# SunS_top.net
KiCad netlist of a schematic drawn in Altium Designer
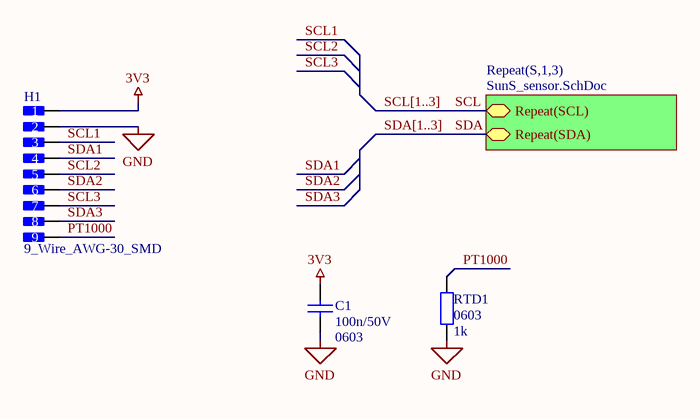
[diagram p0: SunS_top.SchDoc]

(export (version "E")
  (design (tool "Eeschema 10.0.6"))
  (components
    (comp (ref "C1")
      (value "100n/50V")
      (footprint "SMD_Capacitor_0603")
      (description "Ceramic Cap Kemet COTS 100n/50V X7R 0603")
      (fields
        (field (name "MANUFACTURER") "Kemet")
        (field (name "MANUFACTURERPARTNUMBER") "C0603T104K5RALTU")
        (field (name "PACKAGE") "0603")
      )
      (libsource (lib "capacitors") (part "Cer_C0603T104K5RALTU"))
    )
    (comp (ref "H1")
      (value "9_Wire_AWG-30_SMD")
      (footprint "Wire_AWG-30_x9_SMD")
      (description "9 x SMD pads for an AWG-30 wire with stress relief, pitch 1.27mm.")
      (libsource (lib "connectors_printed-circuit-board") (part "Wire_AWG-30_9_SMD"))
    )
    (comp (ref "RTD1")
      (value "1k")
      (footprint "SMD_Resistor_0603")
      (description "PT1000 Vishay PTS060301B100RP100")
      (fields
        (field (name "MANUFACTURER") "Vishay")
        (field (name "MANUFACTURERPARTNUMBER") "PTS060301B100RP100")
        (field (name "PACKAGE") "0603")
      )
      (libsource (lib "resistors") (part "PTS060301B100RP100"))
    )
  )
  (nets
    (net (code "1") (name "/PT1000") (class "Default")
      (node (ref "H1") (pin "9") (pinfunction "9_9") (pintype "passive"))
      (node (ref "RTD1") (pin "1") (pinfunction "1_1") (pintype "passive"))
    )
    (net (code "3") (name "/SCL1") (class "Default")
      (node (ref "H1") (pin "3") (pinfunction "3_3") (pintype "passive"))
    )
    (net (code "4") (name "/SCL2") (class "Default")
      (node (ref "H1") (pin "5") (pinfunction "5_5") (pintype "passive"))
    )
    (net (code "5") (name "/SCL3") (class "Default")
      (node (ref "H1") (pin "7") (pinfunction "7_7") (pintype "passive"))
    )
    (net (code "8") (name "/SDA1") (class "Default")
      (node (ref "H1") (pin "4") (pinfunction "4_4") (pintype "passive"))
    )
    (net (code "9") (name "/SDA2") (class "Default")
      (node (ref "H1") (pin "6") (pinfunction "6_6") (pintype "passive"))
    )
    (net (code "10") (name "/SDA3") (class "Default")
      (node (ref "H1") (pin "8") (pinfunction "8_8") (pintype "passive"))
    )
    (net (code "12") (name "3V3") (class "Default")
      (node (ref "C1") (pin "1") (pinfunction "1_1") (pintype "passive"))
      (node (ref "H1") (pin "1") (pinfunction "1_1") (pintype "passive"))
    )
    (net (code "13") (name "GND") (class "Default")
      (node (ref "C1") (pin "2") (pinfunction "2_2") (pintype "passive"))
      (node (ref "H1") (pin "2") (pinfunction "2_2") (pintype "passive"))
      (node (ref "RTD1") (pin "2") (pinfunction "2_2") (pintype "passive"))
    )
  )
)
